# br215.net
KiCad netlist of a schematic drawn in EAGLE
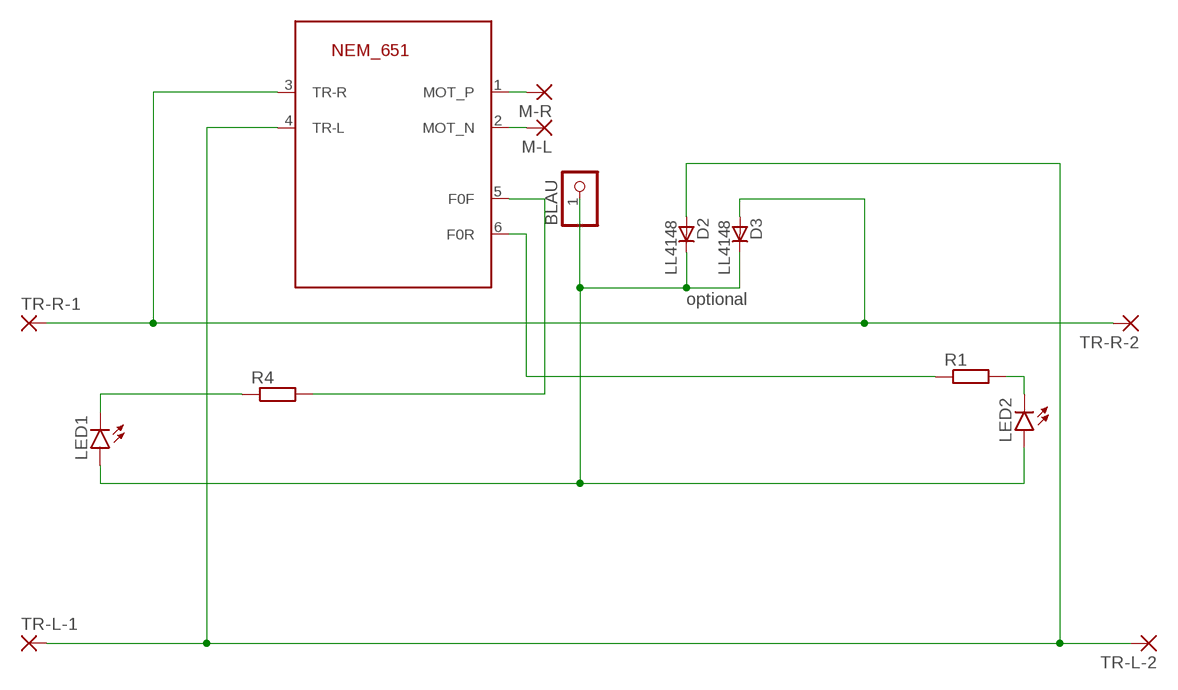
[diagram p0: schematic, sheet 1]

(export (version "E")
  (design (tool "Eeschema 10.0.6"))
  (components
    (comp (ref "651")
      (value "NEM_651-TS")
      (footprint "eagle-import:53047-06")
      (libsource (lib "eagle-import") (part "NEM_651-TS"))
    )
    (comp (ref "BLAU")
      (value "PINHD-1X1")
      (footprint "eagle-import:1X01")
      (libsource (lib "eagle-import") (part "PINHD-1X1"))
    )
    (comp (ref "D2")
      (value "LL4148")
      (footprint "eagle-import:SOD80_DO213AA_MINIMELF")
      (libsource (lib "eagle-import") (part "LL4148"))
    )
    (comp (ref "D3")
      (value "LL4148")
      (footprint "eagle-import:SOD80_DO213AA_MINIMELF")
      (libsource (lib "eagle-import") (part "LL4148"))
    )
    (comp (ref "LED1")
      (value "LED3MM")
      (footprint "eagle-import:LED3MM")
      (libsource (lib "eagle-import") (part "LED3MM"))
    )
    (comp (ref "LED2")
      (value "LED3MM")
      (footprint "eagle-import:LED3MM")
      (libsource (lib "eagle-import") (part "LED3MM"))
    )
    (comp (ref "M-L")
      (value "SMD5")
      (footprint "eagle-import:SMD2,54-5,08")
      (libsource (lib "eagle-import") (part "SMD5"))
    )
    (comp (ref "M-R")
      (value "SMD5")
      (footprint "eagle-import:SMD2,54-5,08")
      (libsource (lib "eagle-import") (part "SMD5"))
    )
    (comp (ref "R1")
      (value "R-EU_R0603")
      (footprint "eagle-import:R0603")
      (libsource (lib "eagle-import") (part "R-EU_R0603"))
    )
    (comp (ref "R4")
      (value "R-EU_R0603")
      (footprint "eagle-import:R0603")
      (libsource (lib "eagle-import") (part "R-EU_R0603"))
    )
    (comp (ref "TR-L-1")
      (value "SMD5")
      (footprint "eagle-import:SMD2,54-5,08")
      (libsource (lib "eagle-import") (part "SMD5"))
    )
    (comp (ref "TR-L-2")
      (value "SMD5")
      (footprint "eagle-import:SMD2,54-5,08")
      (libsource (lib "eagle-import") (part "SMD5"))
    )
    (comp (ref "TR-R-1")
      (value "SMD5")
      (footprint "eagle-import:SMD2,54-5,08")
      (libsource (lib "eagle-import") (part "SMD5"))
    )
    (comp (ref "TR-R-2")
      (value "SMD5")
      (footprint "eagle-import:SMD2,54-5,08")
      (libsource (lib "eagle-import") (part "SMD5"))
    )
  )
  (nets
    (net (code "1") (name "Net-(651-F0F)") (class "Default")
      (node (ref "651") (pin "5") (pinfunction "F0F_5") (pintype "bidirectional"))
      (node (ref "R4") (pin "2") (pinfunction "2_2") (pintype "passive"))
    )
    (net (code "2") (name "Net-(651-F0R)") (class "Default")
      (node (ref "651") (pin "6") (pinfunction "F0R_6") (pintype "bidirectional"))
      (node (ref "R1") (pin "1") (pinfunction "1_1") (pintype "passive"))
    )
    (net (code "3") (name "Net-(651-MOT_N)") (class "Default")
      (node (ref "651") (pin "2") (pinfunction "MOT_N_2") (pintype "bidirectional"))
      (node (ref "M-L") (pin "1") (pinfunction "P_1") (pintype "passive"))
    )
    (net (code "4") (name "Net-(651-MOT_P)") (class "Default")
      (node (ref "651") (pin "1") (pinfunction "MOT_P_1") (pintype "bidirectional"))
      (node (ref "M-R") (pin "1") (pinfunction "P_1") (pintype "passive"))
    )
    (net (code "5") (name "Net-(651-TR-L)") (class "Default")
      (node (ref "651") (pin "4") (pinfunction "TR-L_4") (pintype "bidirectional"))
      (node (ref "D2") (pin "A") (pinfunction "A_A") (pintype "passive"))
      (node (ref "TR-L-1") (pin "1") (pinfunction "P_1") (pintype "passive"))
      (node (ref "TR-L-2") (pin "1") (pinfunction "P_1") (pintype "passive"))
    )
    (net (code "6") (name "Net-(651-TR-R)") (class "Default")
      (node (ref "651") (pin "3") (pinfunction "TR-R_3") (pintype "bidirectional"))
      (node (ref "D3") (pin "A") (pinfunction "A_A") (pintype "passive"))
      (node (ref "TR-R-1") (pin "1") (pinfunction "P_1") (pintype "passive"))
      (node (ref "TR-R-2") (pin "1") (pinfunction "P_1") (pintype "passive"))
    )
    (net (code "7") (name "Net-(BLAU-Pad1)") (class "Default")
      (node (ref "BLAU") (pin "1") (pinfunction "1_1") (pintype "passive"))
      (node (ref "D2") (pin "C") (pinfunction "C_C") (pintype "passive"))
      (node (ref "D3") (pin "C") (pinfunction "C_C") (pintype "passive"))
      (node (ref "LED1") (pin "A") (pinfunction "A_A") (pintype "passive"))
      (node (ref "LED2") (pin "A") (pinfunction "A_A") (pintype "passive"))
    )
    (net (code "8") (name "Net-(LED1-C)") (class "Default")
      (node (ref "LED1") (pin "K") (pinfunction "C_K") (pintype "passive"))
      (node (ref "R4") (pin "1") (pinfunction "1_1") (pintype "passive"))
    )
    (net (code "9") (name "Net-(LED2-C)") (class "Default")
      (node (ref "LED2") (pin "K") (pinfunction "C_K") (pintype "passive"))
      (node (ref "R1") (pin "2") (pinfunction "2_2") (pintype "passive"))
    )
  )
)
